# SSR.net
KiCad netlist of a schematic drawn in Altium Designer
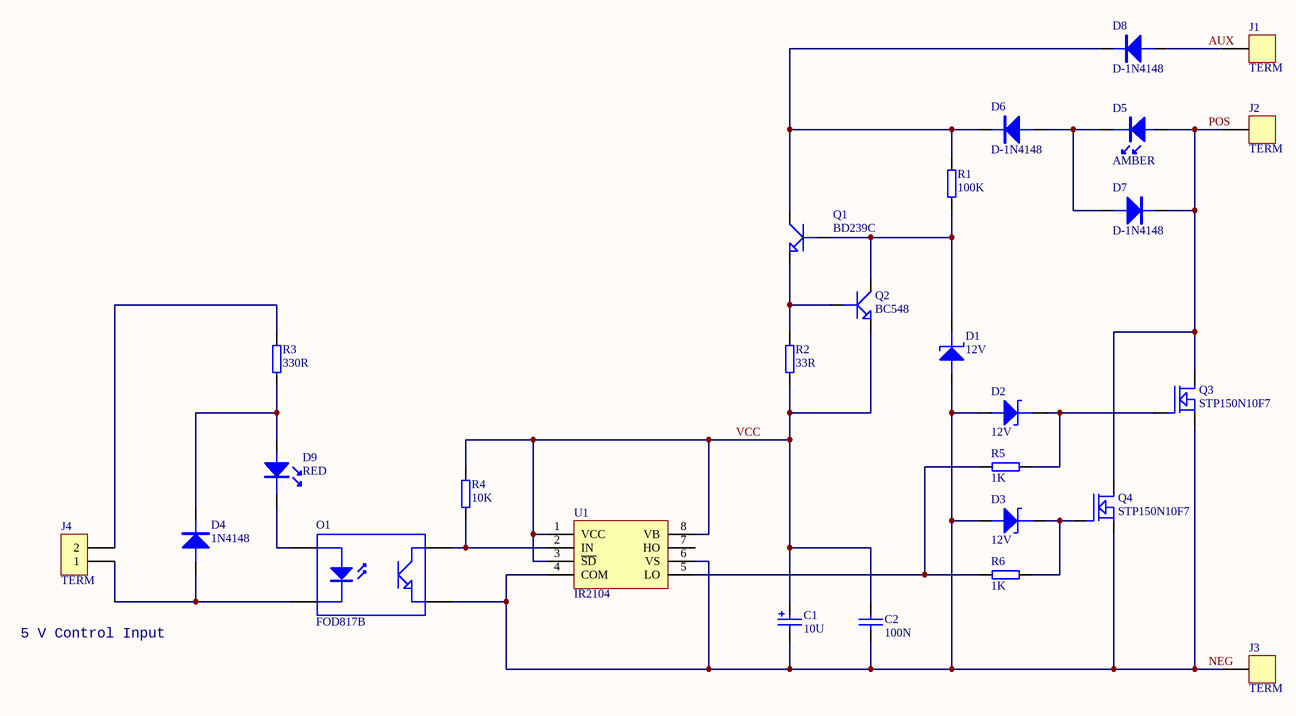
[diagram p0: SSR.SchDoc]

(export (version "E")
  (design (tool "Eeschema 10.0.6"))
  (components
    (comp (ref "C1")
      (value "10U")
      (footprint "RADIAL02P")
      (description "CAP")
      (libsource (lib "SSR") (part "C-A10U"))
    )
    (comp (ref "C2")
      (value "100N")
      (footprint "AXIAL02")
      (description "CAPACITOR")
      (libsource (lib "SSR") (part "C-B100N"))
    )
    (comp (ref "D1")
      (value "12V")
      (footprint "DO35S")
      (description "ZENER DIODE")
      (libsource (lib "SSR") (part "D-BZX79-12"))
    )
    (comp (ref "D2")
      (value "12V")
      (footprint "DO35S")
      (description "ZENER DIODE")
      (libsource (lib "SSR") (part "D-BZX79-12"))
    )
    (comp (ref "D3")
      (value "12V")
      (footprint "DO35S")
      (description "ZENER DIODE")
      (libsource (lib "SSR") (part "D-BZX79-12"))
    )
    (comp (ref "D4") (value "1N4148") (footprint "DO35S") (libsource (lib "SSR") (part "1N4148")))
    (comp (ref "D5")
      (value "AMBER")
      (footprint "LED5MM")
      (description "LED")
      (libsource (lib "SSR") (part "O-AMBER"))
    )
    (comp (ref "D6")
      (value "D-1N4148")
      (footprint "DO35S")
      (description "1N4148")
      (libsource (lib "SSR") (part "D-1N4148"))
    )
    (comp (ref "D7")
      (value "D-1N4148")
      (footprint "DO35S")
      (description "1N4148")
      (libsource (lib "SSR") (part "D-1N4148"))
    )
    (comp (ref "D8")
      (value "D-1N4148")
      (footprint "DO35S")
      (description "1N4148")
      (libsource (lib "SSR") (part "D-1N4148"))
    )
    (comp (ref "D9")
      (value "RED")
      (footprint "LED5MM")
      (description "LED")
      (libsource (lib "SSR") (part "O-RED"))
    )
    (comp (ref "J1")
      (value "TERM")
      (footprint "SCREW3")
      (description "CONNECTOR")
      (libsource (lib "SSR") (part "J-SCREW3"))
    )
    (comp (ref "J2")
      (value "TERM")
      (footprint "SCREW6")
      (description "CONNECTOR")
      (libsource (lib "SSR") (part "J-SCREW6"))
    )
    (comp (ref "J3")
      (value "TERM")
      (footprint "SCREW6")
      (description "CONNECTOR")
      (libsource (lib "SSR") (part "J-SCREW6"))
    )
    (comp (ref "J4")
      (value "TERM")
      (footprint "MKD500S2")
      (description "CONNECTOR")
      (libsource (lib "SSR") (part "J-SCR-2"))
    )
    (comp (ref "O1")
      (value "FOD817B")
      (footprint "DIP4")
      (description "OPTO ISOLATOR")
      (libsource (lib "SSR") (part "O-FOD817B"))
    )
    (comp (ref "Q1") (value "BD239C") (footprint "TO220") (libsource (lib "SSR") (part "Q-BD239C")))
    (comp (ref "Q2") (value "BC548") (footprint "TO92") (libsource (lib "SSR") (part "Q-BC548")))
    (comp (ref "Q3")
      (value "STP150N10F7")
      (footprint "TO220FS")
      (description "MOSFET")
      (libsource (lib "SSR") (part "Q-STP150N10F7"))
    )
    (comp (ref "Q4")
      (value "STP150N10F7")
      (footprint "TO220FS")
      (description "MOSFET")
      (libsource (lib "SSR") (part "Q-STP150N10F7"))
    )
    (comp (ref "R1")
      (value "100K")
      (footprint "AXIAL04")
      (description "RESISTOR")
      (libsource (lib "SSR") (part "R-A100K"))
    )
    (comp (ref "R2")
      (value "33R")
      (footprint "AXIAL04")
      (description "RESISTOR")
      (libsource (lib "SSR") (part "R-A33R"))
    )
    (comp (ref "R3")
      (value "330R")
      (footprint "AXIAL04")
      (description "RESISTOR")
      (libsource (lib "SSR") (part "R-A330R"))
    )
    (comp (ref "R4")
      (value "10K")
      (footprint "AXIAL04")
      (description "RESISTOR")
      (libsource (lib "SSR") (part "R-A10K"))
    )
    (comp (ref "R5")
      (value "1K")
      (footprint "AXIAL04")
      (description "RESISTOR")
      (libsource (lib "SSR") (part "R-A1K"))
    )
    (comp (ref "R6")
      (value "1K")
      (footprint "AXIAL04")
      (description "RESISTOR")
      (libsource (lib "SSR") (part "R-A1K"))
    )
    (comp (ref "U1")
      (value "IR2104")
      (footprint "DIP8")
      (description "GATE DRIVER")
      (libsource (lib "SSR") (part "U-IR2104"))
    )
  )
  (nets
    (net (code "1") (name "/AUX") (class "Default")
      (node (ref "D8") (pin "1") (pinfunction "A_1") (pintype "passive"))
      (node (ref "J1") (pin "1") (pinfunction "1_1") (pintype "passive"))
    )
    (net (code "2") (name "/NEG") (class "Default")
      (node (ref "C1") (pin "2") (pinfunction "2_2") (pintype "passive"))
      (node (ref "C2") (pin "2") (pinfunction "2_2") (pintype "passive"))
      (node (ref "D1") (pin "1") (pinfunction "A_1") (pintype "passive"))
      (node (ref "D2") (pin "1") (pinfunction "A_1") (pintype "passive"))
      (node (ref "D3") (pin "1") (pinfunction "A_1") (pintype "passive"))
      (node (ref "J3") (pin "1") (pinfunction "1_1") (pintype "passive"))
      (node (ref "O1") (pin "3") (pinfunction "E_3") (pintype "passive"))
      (node (ref "Q3") (pin "3") (pinfunction "S_3") (pintype "passive"))
      (node (ref "Q4") (pin "3") (pinfunction "S_3") (pintype "passive"))
      (node (ref "U1") (pin "4") (pinfunction "COM_4") (pintype "passive"))
      (node (ref "U1") (pin "6") (pinfunction "VS_6") (pintype "passive"))
    )
    (net (code "3") (name "/POS") (class "Default")
      (node (ref "D5") (pin "1") (pinfunction "A_1") (pintype "passive"))
      (node (ref "D7") (pin "2") (pinfunction "K_2") (pintype "passive"))
      (node (ref "J2") (pin "1") (pinfunction "1_1") (pintype "passive"))
      (node (ref "Q3") (pin "2") (pinfunction "D_2") (pintype "passive"))
      (node (ref "Q4") (pin "2") (pinfunction "D_2") (pintype "passive"))
    )
    (net (code "4") (name "/VCC") (class "Default")
      (node (ref "C1") (pin "1") (pinfunction "1_1") (pintype "passive"))
      (node (ref "C2") (pin "1") (pinfunction "1_1") (pintype "passive"))
      (node (ref "Q2") (pin "1") (pinfunction "E_1") (pintype "passive"))
      (node (ref "R2") (pin "1") (pinfunction "1_1") (pintype "passive"))
      (node (ref "R4") (pin "2") (pinfunction "2_2") (pintype "passive"))
      (node (ref "U1") (pin "1") (pinfunction "VCC_1") (pintype "passive"))
      (node (ref "U1") (pin "3") (pinfunction "~{SD}_3") (pintype "passive"))
      (node (ref "U1") (pin "8") (pinfunction "VB_8") (pintype "passive"))
    )
    (net (code "5") (name "Net-(D1-K)") (class "Default")
      (node (ref "D1") (pin "2") (pinfunction "K_2") (pintype "passive"))
      (node (ref "Q1") (pin "2") (pinfunction "B_2") (pintype "passive"))
      (node (ref "Q2") (pin "3") (pinfunction "C_3") (pintype "passive"))
      (node (ref "R1") (pin "1") (pinfunction "1_1") (pintype "passive"))
    )
    (net (code "6") (name "Net-(D2-K)") (class "Default")
      (node (ref "D2") (pin "2") (pinfunction "K_2") (pintype "passive"))
      (node (ref "Q3") (pin "1") (pinfunction "G_1") (pintype "passive"))
      (node (ref "R5") (pin "2") (pinfunction "2_2") (pintype "passive"))
    )
    (net (code "7") (name "Net-(D3-K)") (class "Default")
      (node (ref "D3") (pin "2") (pinfunction "K_2") (pintype "passive"))
      (node (ref "Q4") (pin "1") (pinfunction "G_1") (pintype "passive"))
      (node (ref "R6") (pin "2") (pinfunction "2_2") (pintype "passive"))
    )
    (net (code "8") (name "Net-(D4-A)") (class "Default")
      (node (ref "D4") (pin "1") (pinfunction "A_1") (pintype "passive"))
      (node (ref "J4") (pin "1") (pinfunction "1_1") (pintype "passive"))
      (node (ref "O1") (pin "2") (pinfunction "K_2") (pintype "passive"))
    )
    (net (code "9") (name "Net-(D4-K)") (class "Default")
      (node (ref "D4") (pin "2") (pinfunction "K_2") (pintype "passive"))
      (node (ref "D9") (pin "1") (pinfunction "A_1") (pintype "passive"))
      (node (ref "R3") (pin "1") (pinfunction "1_1") (pintype "passive"))
    )
    (net (code "10") (name "Net-(D5-K)") (class "Default")
      (node (ref "D5") (pin "2") (pinfunction "K_2") (pintype "passive"))
      (node (ref "D6") (pin "1") (pinfunction "A_1") (pintype "passive"))
      (node (ref "D7") (pin "1") (pinfunction "A_1") (pintype "passive"))
    )
    (net (code "11") (name "Net-(D6-K)") (class "Default")
      (node (ref "D6") (pin "2") (pinfunction "K_2") (pintype "passive"))
      (node (ref "D8") (pin "2") (pinfunction "K_2") (pintype "passive"))
      (node (ref "Q1") (pin "3") (pinfunction "C_3") (pintype "passive"))
      (node (ref "R1") (pin "2") (pinfunction "2_2") (pintype "passive"))
    )
    (net (code "12") (name "Net-(D9-K)") (class "Default")
      (node (ref "D9") (pin "2") (pinfunction "K_2") (pintype "passive"))
      (node (ref "O1") (pin "1") (pinfunction "A_1") (pintype "passive"))
    )
    (net (code "13") (name "Net-(J4-Pad2)") (class "Default")
      (node (ref "J4") (pin "2") (pinfunction "2_2") (pintype "passive"))
      (node (ref "R3") (pin "2") (pinfunction "2_2") (pintype "passive"))
    )
    (net (code "14") (name "Net-(O1-C)") (class "Default")
      (node (ref "O1") (pin "4") (pinfunction "C_4") (pintype "passive"))
      (node (ref "R4") (pin "1") (pinfunction "1_1") (pintype "passive"))
      (node (ref "U1") (pin "2") (pinfunction "IN_2") (pintype "passive"))
    )
    (net (code "15") (name "Net-(Q1-E)") (class "Default")
      (node (ref "Q1") (pin "1") (pinfunction "E_1") (pintype "passive"))
      (node (ref "Q2") (pin "2") (pinfunction "B_2") (pintype "passive"))
      (node (ref "R2") (pin "2") (pinfunction "2_2") (pintype "passive"))
    )
    (net (code "16") (name "Net-(U1-LO)") (class "Default")
      (node (ref "R5") (pin "1") (pinfunction "1_1") (pintype "passive"))
      (node (ref "R6") (pin "1") (pinfunction "1_1") (pintype "passive"))
      (node (ref "U1") (pin "5") (pinfunction "LO_5") (pintype "passive"))
    )
    (net (code "17") (name "unconnected-(U1-HO-Pad7)") (class "Default")
      (node (ref "U1") (pin "7") (pinfunction "HO_7") (pintype "passive"))
    )
  )
)
